# ST_LINK_V2-1.net
KiCad netlist of a schematic drawn in Altium Designer
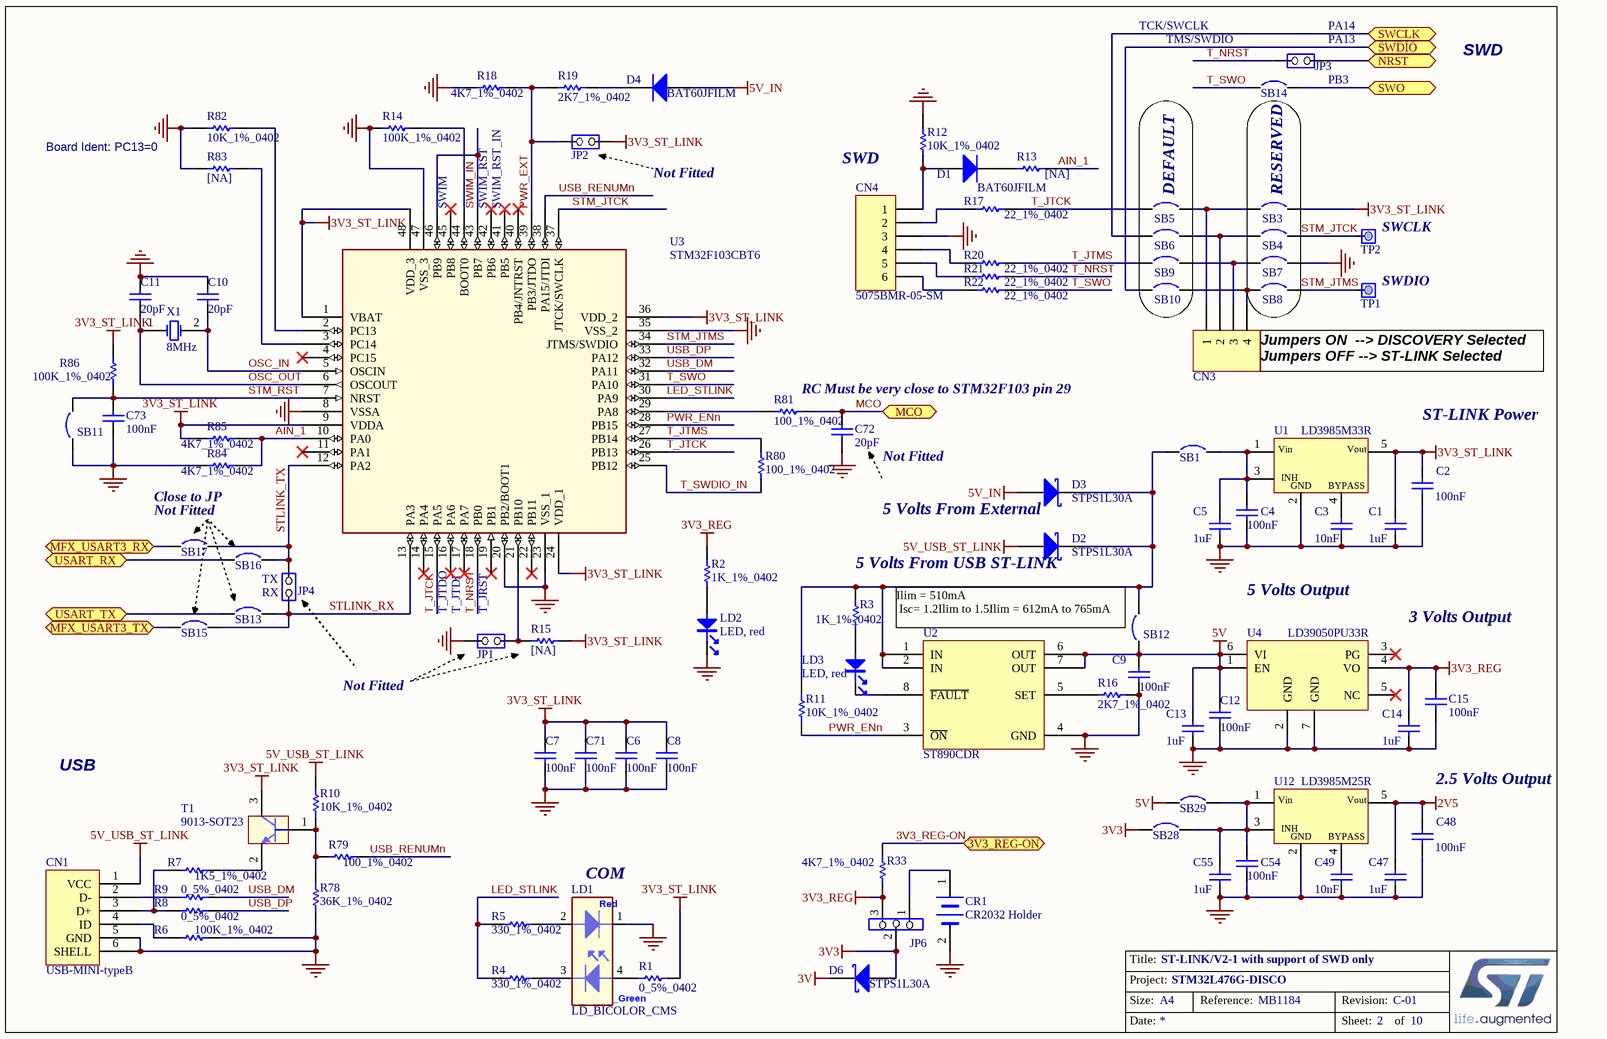
[diagram p0: ST_LINK_V2-1.SCHDOC]

(export (version "E")
  (design (tool "Eeschema 10.0.6"))
  (components
    (comp (ref "C1")
      (value "1uF")
      (footprint "0603C")
      (description "Capacitor,1uF,16V,X5R,10%,0603,YAGEO")
      (libsource (lib "MCD_TOOLS") (part "Cap_1uF_X5R_10%_0603"))
    )
    (comp (ref "C2")
      (value "100nF")
      (footprint "0402C")
      (description "Capacitor,100nF,16V,X7R,10%,0402,YAGEO")
      (libsource (lib "MCD_TOOLS") (part "Cap_100nF_X7R_10%_0402"))
    )
    (comp (ref "C3")
      (value "10nF")
      (footprint "0603C")
      (description "Capacitor,10nF,50V,X7R,10%,0603,YAGEO")
      (libsource (lib "MCD_TOOLS") (part "Cap_10nF_X7R_10%_0603"))
    )
    (comp (ref "C4")
      (value "100nF")
      (footprint "0402C")
      (description "Capacitor,100nF,16V,X7R,10%,0402,YAGEO")
      (libsource (lib "MCD_TOOLS") (part "Cap_100nF_X7R_10%_0402"))
    )
    (comp (ref "C5")
      (value "1uF")
      (footprint "0603C")
      (description "Capacitor,1uF,16V,X5R,10%,0603,YAGEO")
      (libsource (lib "MCD_TOOLS") (part "Cap_1uF_X5R_10%_0603"))
    )
    (comp (ref "C6")
      (value "100nF")
      (footprint "0402C")
      (description "Capacitor,100nF,16V,X7R,10%,0402,YAGEO")
      (libsource (lib "MCD_TOOLS") (part "Cap_100nF_X7R_10%_0402"))
    )
    (comp (ref "C7")
      (value "100nF")
      (footprint "0402C")
      (description "Capacitor,100nF,16V,X7R,10%,0402,YAGEO")
      (libsource (lib "MCD_TOOLS") (part "Cap_100nF_X7R_10%_0402"))
    )
    (comp (ref "C8")
      (value "100nF")
      (footprint "0402C")
      (description "Capacitor,100nF,16V,X7R,10%,0402,YAGEO")
      (libsource (lib "MCD_TOOLS") (part "Cap_100nF_X7R_10%_0402"))
    )
    (comp (ref "C9")
      (value "100nF")
      (footprint "0402C")
      (description "Capacitor,100nF,16V,X7R,10%,0402,YAGEO")
      (libsource (lib "MCD_TOOLS") (part "Cap_100nF_X7R_10%_0402"))
    )
    (comp (ref "C10")
      (value "20pF")
      (footprint "0402C")
      (description "Capacitor,20pF,50V,NPO,5%,0402,YAGEO")
      (libsource (lib "MCD_TOOLS") (part "Cap_20pF_NPO_5%_0402"))
    )
    (comp (ref "C11")
      (value "20pF")
      (footprint "0402C")
      (description "Capacitor,20pF,50V,NPO,5%,0402,YAGEO")
      (libsource (lib "MCD_TOOLS") (part "Cap_20pF_NPO_5%_0402"))
    )
    (comp (ref "C12")
      (value "100nF")
      (footprint "0402C")
      (description "Capacitor,100nF,16V,X7R,10%,0402,YAGEO")
      (libsource (lib "MCD_TOOLS") (part "Cap_100nF_X7R_10%_0402"))
    )
    (comp (ref "C13")
      (value "1uF")
      (footprint "0603C")
      (description "Capacitor,1uF,16V,X5R,10%,0603,YAGEO")
      (libsource (lib "MCD_TOOLS") (part "Cap_1uF_X5R_10%_0603"))
    )
    (comp (ref "C14")
      (value "1uF")
      (footprint "0603C")
      (description "Capacitor,1uF,16V,X5R,10%,0603,YAGEO")
      (libsource (lib "MCD_TOOLS") (part "Cap_1uF_X5R_10%_0603"))
    )
    (comp (ref "C15")
      (value "100nF")
      (footprint "0402C")
      (description "Capacitor,100nF,16V,X7R,10%,0402,YAGEO")
      (libsource (lib "MCD_TOOLS") (part "Cap_100nF_X7R_10%_0402"))
    )
    (comp (ref "C47")
      (value "1uF")
      (footprint "0603C")
      (description "Capacitor,1uF,16V,X5R,10%,0603,YAGEO")
      (libsource (lib "MCD_TOOLS") (part "Cap_1uF_X5R_10%_0603"))
    )
    (comp (ref "C48")
      (value "100nF")
      (footprint "0402C")
      (description "Capacitor,100nF,16V,X7R,10%,0402,YAGEO")
      (libsource (lib "MCD_TOOLS") (part "Cap_100nF_X7R_10%_0402"))
    )
    (comp (ref "C49")
      (value "10nF")
      (footprint "0603C")
      (description "Capacitor,10nF,50V,X7R,10%,0603,YAGEO")
      (libsource (lib "MCD_TOOLS") (part "Cap_10nF_X7R_10%_0603"))
    )
    (comp (ref "C54")
      (value "100nF")
      (footprint "0402C")
      (description "Capacitor,100nF,16V,X7R,10%,0402,YAGEO")
      (libsource (lib "MCD_TOOLS") (part "Cap_100nF_X7R_10%_0402"))
    )
    (comp (ref "C55")
      (value "1uF")
      (footprint "0603C")
      (description "Capacitor,1uF,16V,X5R,10%,0603,YAGEO")
      (libsource (lib "MCD_TOOLS") (part "Cap_1uF_X5R_10%_0603"))
    )
    (comp (ref "C71")
      (value "100nF")
      (footprint "0402C")
      (description "Capacitor,100nF,16V,X7R,10%,0402,YAGEO")
      (libsource (lib "MCD_TOOLS") (part "Cap_100nF_X7R_10%_0402"))
    )
    (comp (ref "C72")
      (value "20pF")
      (footprint "0402C")
      (description "Capacitor,20pF,50V,NPO,5%,0402,YAGEO")
      (libsource (lib "MCD_TOOLS") (part "Cap_20pF_NPO_5%_0402"))
    )
    (comp (ref "C73")
      (value "100nF")
      (footprint "0402C")
      (description "Capacitor,100nF,16V,X7R,10%,0402,YAGEO")
      (libsource (lib "MCD_TOOLS") (part "Cap_100nF_X7R_10%_0402"))
    )
    (comp (ref "CN1")
      (value "USB-MINI-typeB")
      (footprint "USB-MINI-B-SMD")
      (description "USB-MINI-typeB connector")
      (libsource (lib "MCD_TOOLS") (part "USB-MINI-typeB connector"))
    )
    (comp (ref "CN3")
      (value "Header 4")
      (footprint "Header 4")
      (description "Header, 4-Pin")
      (fields (field (name "PUBLISHER") "Altium Limited"))
      (libsource (lib "MCD_TOOLS") (part "Header 4"))
    )
    (comp (ref "CN4")
      (value "5075BMR-05-SM")
      (footprint "HDR1X6")
      (description "Header, 6-Pin")
      (fields (field (name "PUBLISHER") "Altium Limited"))
      (libsource (lib "MCD_TOOLS") (part "Header 6"))
    )
    (comp (ref "CR1")
      (value "CR2032 Holder")
      (footprint "CR2032/SMT")
      (description "CR2032 socket, S8421-45R")
      (libsource (lib "MCD_TOOLS") (part "BATT_2032"))
    )
    (comp (ref "D1")
      (value "BAT60JFILM")
      (footprint "SOD323/A")
      (libsource (lib "MCD_TOOLS") (part "BAT60JFILM"))
    )
    (comp (ref "D2")
      (value "STPS1L30A")
      (footprint "SMA")
      (description "Low Drop power Schottky rectifier")
      (libsource (lib "MCD_TOOLS") (part "STPS1L30A"))
    )
    (comp (ref "D3")
      (value "STPS1L30A")
      (footprint "SMA")
      (description "Low Drop power Schottky rectifier")
      (libsource (lib "MCD_TOOLS") (part "STPS1L30A"))
    )
    (comp (ref "D4")
      (value "BAT60JFILM")
      (footprint "SOD323/A")
      (libsource (lib "MCD_TOOLS") (part "BAT60JFILM"))
    )
    (comp (ref "D6")
      (value "STPS1L30A")
      (footprint "SMA")
      (description "Low Drop power Schottky rectifier")
      (libsource (lib "MCD_TOOLS") (part "STPS1L30A"))
    )
    (comp (ref "JP1")
      (value "Jumper 2 pins")
      (footprint "SIP2/2.54")
      (libsource (lib "MCD_TOOLS") (part "Jumper2"))
    )
    (comp (ref "JP2")
      (value "Jumper 2 pins")
      (footprint "SIP2/2.54")
      (libsource (lib "MCD_TOOLS") (part "Jumper2"))
    )
    (comp (ref "JP3")
      (value "Jumper 2 pins")
      (footprint "SIP2/2.54")
      (libsource (lib "MCD_TOOLS") (part "Jumper2"))
    )
    (comp (ref "JP4")
      (value "Jumper 2 pins")
      (footprint "SIP2/2.54")
      (libsource (lib "MCD_TOOLS") (part "Jumper2"))
    )
    (comp (ref "JP6")
      (value "Jumper 3 pins")
      (footprint "SIP3")
      (libsource (lib "MCD_TOOLS") (part "Jumper3"))
    )
    (comp (ref "LD1")
      (value "LD_BICOLOR_CMS")
      (footprint "HSMF-A201")
      (description "Bicolor Led")
      (libsource (lib "MCD_TOOLS") (part "LD_BICOLOR_CMS"))
    )
    (comp (ref "LD2")
      (value "LED, red")
      (footprint "0603D")
      (description "LED, red, 0603")
      (libsource (lib "MCD_TOOLS") (part "LED_red"))
    )
    (comp (ref "LD3")
      (value "LED, red")
      (footprint "0603D")
      (description "LED, red, 0603")
      (libsource (lib "MCD_TOOLS") (part "LED_red"))
    )
    (comp (ref "R1")
      (value "0_5%_0402")
      (footprint "0402R")
      (description "Resistor,0,0402,5%,YAGEO")
      (libsource (lib "MCD_TOOLS") (part "Res_0_5%_0402"))
    )
    (comp (ref "R2")
      (value "1K_1%_0402")
      (footprint "0402R")
      (description "Resistor,1K,0402,1%,YAGEO")
      (libsource (lib "MCD_TOOLS") (part "Res_1K_1%_0402"))
    )
    (comp (ref "R3")
      (value "1K_1%_0402")
      (footprint "0402R")
      (description "Resistor,1K,0402,1%,YAGEO")
      (libsource (lib "MCD_TOOLS") (part "Res_1K_1%_0402"))
    )
    (comp (ref "R4")
      (value "330_1%_0402")
      (footprint "0402R")
      (description "Resistor,330,0402,1%,YAGEO")
      (libsource (lib "MCD_TOOLS") (part "Res_330_1%_0402"))
    )
    (comp (ref "R5")
      (value "330_1%_0402")
      (footprint "0402R")
      (description "Resistor,330,0402,1%,YAGEO")
      (libsource (lib "MCD_TOOLS") (part "Res_330_1%_0402"))
    )
    (comp (ref "R6")
      (value "100K_1%_0402")
      (footprint "0402R")
      (description "Resistor,100K,0402,1%,YAGEO")
      (libsource (lib "MCD_TOOLS") (part "Res_100K_1%_0402"))
    )
    (comp (ref "R7")
      (value "1K5_1%_0402")
      (footprint "0402R")
      (description "Resistor,1K5,0402,1%,YAGEO")
      (libsource (lib "MCD_TOOLS") (part "Res_1K5_1%_0402"))
    )
    (comp (ref "R8")
      (value "0_5%_0402")
      (footprint "0402R")
      (description "Resistor,0,0402,5%,YAGEO")
      (libsource (lib "MCD_TOOLS") (part "Res_0_5%_0402"))
    )
    (comp (ref "R9")
      (value "0_5%_0402")
      (footprint "0402R")
      (description "Resistor,0,0402,5%,YAGEO")
      (libsource (lib "MCD_TOOLS") (part "Res_0_5%_0402"))
    )
    (comp (ref "R10")
      (value "10K_1%_0402")
      (footprint "0402R")
      (description "Resistor,10K,0402,1%,YAGEO")
      (libsource (lib "MCD_TOOLS") (part "Res_10K_1%_0402"))
    )
    (comp (ref "R11")
      (value "10K_1%_0402")
      (footprint "0402R")
      (description "Resistor,10K,0402,1%,YAGEO")
      (libsource (lib "MCD_TOOLS") (part "Res_10K_1%_0402"))
    )
    (comp (ref "R12")
      (value "10K_1%_0402")
      (footprint "0402R")
      (description "Resistor,10K,0402,1%,YAGEO")
      (libsource (lib "MCD_TOOLS") (part "Res_10K_1%_0402"))
    )
    (comp (ref "R13")
      (value "[NA]")
      (footprint "0402R")
      (description "Resistor,[NA],0402")
      (libsource (lib "MCD_TOOLS") (part "Res_NA_0402"))
    )
    (comp (ref "R14")
      (value "100K_1%_0402")
      (footprint "0402R")
      (description "Resistor,100K,0402,1%,YAGEO")
      (libsource (lib "MCD_TOOLS") (part "Res_100K_1%_0402"))
    )
    (comp (ref "R15")
      (value "[NA]")
      (footprint "0402R")
      (description "Resistor,[NA],0402")
      (libsource (lib "MCD_TOOLS") (part "Res_NA_0402"))
    )
    (comp (ref "R16")
      (value "2K7_1%_0402")
      (footprint "0402R")
      (description "Resistor,2K7,0402,1%,YAGEO")
      (libsource (lib "MCD_TOOLS") (part "Res_2K7_1%_0402"))
    )
    (comp (ref "R17")
      (value "22_1%_0402")
      (footprint "0402R")
      (description "Resistor,22,0402,1%,YAGEO")
      (libsource (lib "MCD_TOOLS") (part "Res_22_1%_0402"))
    )
    (comp (ref "R18")
      (value "4K7_1%_0402")
      (footprint "0402R")
      (description "Resistor,4K7,0402,1%,YAGEO")
      (libsource (lib "MCD_TOOLS") (part "Res_4K7_1%_0402"))
    )
    (comp (ref "R19")
      (value "2K7_1%_0402")
      (footprint "0402R")
      (description "Resistor,2K7,0402,1%,YAGEO")
      (libsource (lib "MCD_TOOLS") (part "Res_2K7_1%_0402"))
    )
    (comp (ref "R20")
      (value "22_1%_0402")
      (footprint "0402R")
      (description "Resistor,22,0402,1%,YAGEO")
      (libsource (lib "MCD_TOOLS") (part "Res_22_1%_0402"))
    )
    (comp (ref "R21")
      (value "22_1%_0402")
      (footprint "0402R")
      (description "Resistor,22,0402,1%,YAGEO")
      (libsource (lib "MCD_TOOLS") (part "Res_22_1%_0402"))
    )
    (comp (ref "R22")
      (value "22_1%_0402")
      (footprint "0402R")
      (description "Resistor,22,0402,1%,YAGEO")
      (libsource (lib "MCD_TOOLS") (part "Res_22_1%_0402"))
    )
    (comp (ref "R33")
      (value "4K7_1%_0402")
      (footprint "0402R")
      (description "Resistor,4K7,0402,1%,YAGEO")
      (libsource (lib "MCD_TOOLS") (part "Res_4K7_1%_0402"))
    )
    (comp (ref "R78")
      (value "36K_1%_0402")
      (footprint "0402R")
      (description "Resistor,36K,0402,1%,YAGEO")
      (libsource (lib "MCD_TOOLS") (part "Res_36K_1%_0402"))
    )
    (comp (ref "R79")
      (value "100_1%_0402")
      (footprint "0402R")
      (description "Resistor,100,0402,1%,YAGEO")
      (libsource (lib "MCD_TOOLS") (part "Res_100_1%_0402"))
    )
    (comp (ref "R80")
      (value "100_1%_0402")
      (footprint "0402R")
      (description "Resistor,100,0402,1%,YAGEO")
      (libsource (lib "MCD_TOOLS") (part "Res_100_1%_0402"))
    )
    (comp (ref "R81")
      (value "100_1%_0402")
      (footprint "0402R")
      (description "Resistor,100,0402,1%,YAGEO")
      (libsource (lib "MCD_TOOLS") (part "Res_100_1%_0402"))
    )
    (comp (ref "R82")
      (value "10K_1%_0402")
      (footprint "0402R")
      (description "Resistor,10K,0402,1%,YAGEO")
      (libsource (lib "MCD_TOOLS") (part "Res_10K_1%_0402"))
    )
    (comp (ref "R83")
      (value "[NA]")
      (footprint "0402R")
      (description "Resistor,[NA],0402")
      (libsource (lib "MCD_TOOLS") (part "Res_NA_0402"))
    )
    (comp (ref "R84")
      (value "4K7_1%_0402")
      (footprint "0402R")
      (description "Resistor,4K7,0402,1%,YAGEO")
      (libsource (lib "MCD_TOOLS") (part "Res_4K7_1%_0402"))
    )
    (comp (ref "R85")
      (value "4K7_1%_0402")
      (footprint "0402R")
      (description "Resistor,4K7,0402,1%,YAGEO")
      (libsource (lib "MCD_TOOLS") (part "Res_4K7_1%_0402"))
    )
    (comp (ref "R86")
      (value "100K_1%_0402")
      (footprint "0402R")
      (description "Resistor,100K,0402,1%,YAGEO")
      (libsource (lib "MCD_TOOLS") (part "Res_100K_1%_0402"))
    )
    (comp (ref "SB1")
      (value "Circuit Breaker")
      (footprint "JP2_SMD")
      (libsource (lib "MCD_TOOLS") (part "Circuit Breaker"))
    )
    (comp (ref "SB3")
      (value "Circuit Breaker")
      (footprint "JP2_SMD")
      (libsource (lib "MCD_TOOLS") (part "Circuit Breaker"))
    )
    (comp (ref "SB4")
      (value "Circuit Breaker")
      (footprint "JP2_SMD")
      (libsource (lib "MCD_TOOLS") (part "Circuit Breaker"))
    )
    (comp (ref "SB5")
      (value "Circuit Breaker")
      (footprint "JP2_SMD")
      (libsource (lib "MCD_TOOLS") (part "Circuit Breaker"))
    )
    (comp (ref "SB6")
      (value "Circuit Breaker")
      (footprint "JP2_SMD")
      (libsource (lib "MCD_TOOLS") (part "Circuit Breaker"))
    )
    (comp (ref "SB7")
      (value "Circuit Breaker")
      (footprint "JP2_SMD")
      (libsource (lib "MCD_TOOLS") (part "Circuit Breaker"))
    )
    (comp (ref "SB8")
      (value "Circuit Breaker")
      (footprint "JP2_SMD")
      (libsource (lib "MCD_TOOLS") (part "Circuit Breaker"))
    )
    (comp (ref "SB9")
      (value "Circuit Breaker")
      (footprint "JP2_SMD")
      (libsource (lib "MCD_TOOLS") (part "Circuit Breaker"))
    )
    (comp (ref "SB10")
      (value "Circuit Breaker")
      (footprint "JP2_SMD")
      (libsource (lib "MCD_TOOLS") (part "Circuit Breaker"))
    )
    (comp (ref "SB11")
      (value "Circuit Breaker")
      (footprint "JP2_SMD")
      (libsource (lib "MCD_TOOLS") (part "Circuit Breaker"))
    )
    (comp (ref "SB12")
      (value "Circuit Breaker")
      (footprint "JP2_SMD")
      (libsource (lib "MCD_TOOLS") (part "Circuit Breaker"))
    )
    (comp (ref "SB13")
      (value "Circuit Breaker")
      (footprint "JP2_SMD")
      (libsource (lib "MCD_TOOLS") (part "Circuit Breaker"))
    )
    (comp (ref "SB14")
      (value "Circuit Breaker")
      (footprint "JP2_SMD")
      (libsource (lib "MCD_TOOLS") (part "Circuit Breaker"))
    )
    (comp (ref "SB15")
      (value "Circuit Breaker")
      (footprint "JP2_SMD")
      (libsource (lib "MCD_TOOLS") (part "Circuit Breaker"))
    )
    (comp (ref "SB16")
      (value "Circuit Breaker")
      (footprint "JP2_SMD")
      (libsource (lib "MCD_TOOLS") (part "Circuit Breaker"))
    )
    (comp (ref "SB17")
      (value "Circuit Breaker")
      (footprint "JP2_SMD")
      (libsource (lib "MCD_TOOLS") (part "Circuit Breaker"))
    )
    (comp (ref "SB28")
      (value "Circuit Breaker")
      (footprint "JP2_SMD")
      (libsource (lib "MCD_TOOLS") (part "Circuit Breaker"))
    )
    (comp (ref "SB29")
      (value "Circuit Breaker")
      (footprint "JP2_SMD")
      (libsource (lib "MCD_TOOLS") (part "Circuit Breaker"))
    )
    (comp (ref "T1")
      (value "9013-SOT23")
      (footprint "SOT23")
      (description "NPN Bipolar Transistor")
      (libsource (lib "MCD_TOOLS") (part "9013-SOT23"))
    )
    (comp (ref "TP1")
      (value "Test point 1 pin with hole")
      (footprint "SIP1/2.54")
      (description "Test Point")
      (libsource (lib "MCD_TOOLS") (part "TP1"))
    )
    (comp (ref "TP2")
      (value "Test point 1 pin with hole")
      (footprint "SIP1/2.54")
      (description "Test Point")
      (libsource (lib "MCD_TOOLS") (part "TP1"))
    )
    (comp (ref "U1")
      (value "LD3985M33R")
      (footprint "SOT-23-5L")
      (description "Ultra low drop-low noise BiCMOS voltage, regulators low ESR capacitors compatible")
      (libsource (lib "MCD_TOOLS") (part "LD3985M33R"))
    )
    (comp (ref "U2")
      (value "ST890CDR")
      (footprint "SO-8")
      (description "1.2 A current limited high-side power switch with thermal shutdown")
      (libsource (lib "MCD_TOOLS") (part "ST890CDR"))
    )
    (comp (ref "U3")
      (value "STM32F103CBT6")
      (footprint "QFP48 7x7")
      (description "Medium-density performance line ARM-based 32-bit MCU with 128KB Flash")
      (libsource (lib "MCD_TOOLS") (part "STM32F103CBT6"))
    )
    (comp (ref "U4")
      (value "LD39050PU33R")
      (footprint "DFN6_3x3")
      (description "Ultra low drop-low , 500 mA low quiescent current")
      (libsource (lib "MCD_TOOLS") (part "LD39050P"))
    )
    (comp (ref "U12")
      (value "LD3985M25R")
      (footprint "SOT-23-5L")
      (description "Ultra low drop-low noise BiCMOS voltage, regulators low ESR capacitors compatible")
      (libsource (lib "MCD_TOOLS") (part "LD3985M25R"))
    )
    (comp (ref "X1")
      (value "8MHz")
      (footprint "XTAL1")
      (description "Crystal Oscillator,8Mhz,20PF,20PPM,-10-70 degree,DIP,HC-49S")
      (libsource (lib "MCD_TOOLS") (part "XTAL_8MHZ_20PPM"))
    )
  )
  (nets
    (net (code "1") (name "/3V3_REG-ON") (class "Default")
      (node (ref "R33") (pin "2") (pinfunction "2_2") (pintype "passive"))
    )
    (net (code "2") (name "/AIN_1") (class "Default")
      (node (ref "R13") (pin "2") (pinfunction "2_2") (pintype "passive"))
      (node (ref "R84") (pin "2") (pinfunction "2_2") (pintype "passive"))
      (node (ref "R85") (pin "2") (pinfunction "2_2") (pintype "passive"))
      (node (ref "U3") (pin "10") (pinfunction "PA0_10") (pintype "bidirectional"))
    )
    (net (code "3") (name "/LED_STLINK") (class "Default")
      (node (ref "R4") (pin "1") (pinfunction "1_1") (pintype "passive"))
      (node (ref "R5") (pin "1") (pinfunction "1_1") (pintype "passive"))
      (node (ref "U3") (pin "30") (pinfunction "PA9_30") (pintype "bidirectional"))
    )
    (net (code "4") (name "/MCO") (class "Default")
      (node (ref "C72") (pin "1") (pinfunction "1_1") (pintype "passive"))
      (node (ref "R81") (pin "2") (pinfunction "2_2") (pintype "passive"))
    )
    (net (code "5") (name "/MFX_USART3_RX") (class "Default")
      (node (ref "SB17") (pin "1") (pinfunction "1_1") (pintype "passive"))
    )
    (net (code "6") (name "/MFX_USART3_TX") (class "Default")
      (node (ref "SB15") (pin "1") (pinfunction "1_1") (pintype "passive"))
    )
    (net (code "7") (name "/NRST") (class "Default")
      (node (ref "JP3") (pin "2") (pinfunction "NO_2") (pintype "passive"))
    )
    (net (code "8") (name "/OSC_IN") (class "Default")
      (node (ref "C10") (pin "2") (pinfunction "2_2") (pintype "passive"))
      (node (ref "U3") (pin "5") (pinfunction "OSCIN_5") (pintype "input"))
      (node (ref "X1") (pin "2") (pinfunction "OSC2_2") (pintype "passive"))
    )
    (net (code "9") (name "/OSC_OUT") (class "Default")
      (node (ref "C11") (pin "2") (pinfunction "2_2") (pintype "passive"))
      (node (ref "U3") (pin "6") (pinfunction "OSCOUT_6") (pintype "output"))
      (node (ref "X1") (pin "1") (pinfunction "OSC1_1") (pintype "passive"))
    )
    (net (code "10") (name "/PWR_ENn") (class "Default")
      (node (ref "R11") (pin "1") (pinfunction "1_1") (pintype "passive"))
      (node (ref "U2") (pin "3") (pinfunction "~{ON}_3") (pintype "passive"))
      (node (ref "U3") (pin "28") (pinfunction "PB15_28") (pintype "bidirectional"))
    )
    (net (code "11") (name "/PWR_EXT") (class "Default")
      (node (ref "JP2") (pin "1") (pinfunction "COMMON_1") (pintype "passive"))
      (node (ref "R18") (pin "2") (pinfunction "2_2") (pintype "passive"))
      (node (ref "R19") (pin "1") (pinfunction "1_1") (pintype "passive"))
      (node (ref "U3") (pin "39") (pinfunction "PB3/JTDO_39") (pintype "bidirectional"))
    )
    (net (code "12") (name "/STLINK_RX") (class "Default")
      (node (ref "JP4") (pin "1") (pinfunction "COMMON_1") (pintype "passive"))
      (node (ref "SB13") (pin "2") (pinfunction "2_2") (pintype "passive"))
      (node (ref "SB15") (pin "2") (pinfunction "2_2") (pintype "passive"))
      (node (ref "U3") (pin "13") (pinfunction "PA3_13") (pintype "bidirectional"))
    )
    (net (code "13") (name "/STLINK_TX") (class "Default")
      (node (ref "JP4") (pin "2") (pinfunction "NO_2") (pintype "passive"))
      (node (ref "SB16") (pin "2") (pinfunction "2_2") (pintype "passive"))
      (node (ref "SB17") (pin "2") (pinfunction "2_2") (pintype "passive"))
      (node (ref "U3") (pin "12") (pinfunction "PA2_12") (pintype "bidirectional"))
    )
    (net (code "14") (name "/STM_JTCK") (class "Default")
      (node (ref "SB4") (pin "2") (pinfunction "2_2") (pintype "passive"))
      (node (ref "TP2") (pin "1") (pinfunction "COMMON_1") (pintype "passive"))
      (node (ref "U3") (pin "37") (pinfunction "JTCK/SWCLK_37") (pintype "bidirectional"))
    )
    (net (code "15") (name "/STM_JTMS") (class "Default")
      (node (ref "SB8") (pin "2") (pinfunction "2_2") (pintype "passive"))
      (node (ref "TP1") (pin "1") (pinfunction "COMMON_1") (pintype "passive"))
      (node (ref "U3") (pin "34") (pinfunction "JTMS/SWDIO_34") (pintype "bidirectional"))
    )
    (net (code "16") (name "/STM_RST") (class "Default")
      (node (ref "C73") (pin "2") (pinfunction "2_2") (pintype "passive"))
      (node (ref "R86") (pin "1") (pinfunction "1_1") (pintype "passive"))
      (node (ref "SB11") (pin "2") (pinfunction "2_2") (pintype "passive"))
      (node (ref "U3") (pin "7") (pinfunction "NRST_7") (pintype "input"))
    )
    (net (code "17") (name "/SWCLK") (class "Default")
      (node (ref "SB6") (pin "1") (pinfunction "1_1") (pintype "passive"))
    )
    (net (code "18") (name "/SWDIO") (class "Default")
      (node (ref "SB10") (pin "1") (pinfunction "1_1") (pintype "passive"))
    )
    (net (code "19") (name "/SWIM_IN") (class "Default")
      (node (ref "U3") (pin "43") (pinfunction "PB7_43") (pintype "bidirectional"))
      (node (ref "U3") (pin "46") (pinfunction "PB9_46") (pintype "bidirectional"))
    )
    (net (code "20") (name "/SWO") (class "Default")
      (node (ref "SB14") (pin "2") (pinfunction "2_2") (pintype "passive"))
    )
    (net (code "21") (name "/T_JTCK") (class "Default")
      (node (ref "R17") (pin "2") (pinfunction "2_2") (pintype "passive"))
      (node (ref "SB5") (pin "1") (pinfunction "1_1") (pintype "passive"))
      (node (ref "U3") (pin "15") (pinfunction "PA5_15") (pintype "bidirectional"))
      (node (ref "U3") (pin "26") (pinfunction "PB13_26") (pintype "bidirectional"))
    )
    (net (code "22") (name "/T_JTMS") (class "Default")
      (node (ref "R20") (pin "2") (pinfunction "2_2") (pintype "passive"))
      (node (ref "R80") (pin "2") (pinfunction "2_2") (pintype "passive"))
      (node (ref "SB9") (pin "1") (pinfunction "1_1") (pintype "passive"))
      (node (ref "U3") (pin "27") (pinfunction "PB14_27") (pintype "bidirectional"))
    )
    (net (code "23") (name "/T_NRST") (class "Default")
      (node (ref "JP3") (pin "1") (pinfunction "COMMON_1") (pintype "passive"))
      (node (ref "R21") (pin "2") (pinfunction "2_2") (pintype "passive"))
      (node (ref "U3") (pin "18") (pinfunction "PB0_18") (pintype "bidirectional"))
    )
    (net (code "24") (name "/T_SWDIO_IN") (class "Default")
      (node (ref "R80") (pin "1") (pinfunction "1_1") (pintype "passive"))
      (node (ref "U3") (pin "25") (pinfunction "PB12_25") (pintype "bidirectional"))
    )
    (net (code "25") (name "/T_SWO") (class "Default")
      (node (ref "R22") (pin "2") (pinfunction "2_2") (pintype "passive"))
      (node (ref "SB14") (pin "1") (pinfunction "1_1") (pintype "passive"))
      (node (ref "U3") (pin "31") (pinfunction "PA10_31") (pintype "bidirectional"))
    )
    (net (code "26") (name "/USART_RX") (class "Default")
      (node (ref "SB16") (pin "1") (pinfunction "1_1") (pintype "passive"))
    )
    (net (code "27") (name "/USART_TX") (class "Default")
      (node (ref "SB13") (pin "1") (pinfunction "1_1") (pintype "passive"))
    )
    (net (code "28") (name "/USB_DM") (class "Default")
      (node (ref "R9") (pin "2") (pinfunction "2_2") (pintype "passive"))
      (node (ref "U3") (pin "32") (pinfunction "PA11_32") (pintype "bidirectional"))
    )
    (net (code "29") (name "/USB_DP") (class "Default")
      (node (ref "R8") (pin "2") (pinfunction "2_2") (pintype "passive"))
      (node (ref "U3") (pin "33") (pinfunction "PA12_33") (pintype "bidirectional"))
    )
    (net (code "30") (name "/USB_RENUMn") (class "Default")
      (node (ref "R79") (pin "2") (pinfunction "2_2") (pintype "passive"))
      (node (ref "U3") (pin "38") (pinfunction "PA15/JTDI_38") (pintype "bidirectional"))
    )
    (net (code "31") (name "2V5") (class "Default")
      (node (ref "C47") (pin "1") (pinfunction "1_1") (pintype "passive"))
      (node (ref "C48") (pin "2") (pinfunction "2_2") (pintype "passive"))
      (node (ref "U12") (pin "5") (pinfunction "Vout_5") (pintype "passive"))
    )
    (net (code "32") (name "3V") (class "Default")
      (node (ref "D6") (pin "2") (pinfunction "K_2") (pintype "passive"))
    )
    (net (code "33") (name "3V3") (class "Default")
      (node (ref "D6") (pin "1") (pinfunction "A_1") (pintype "passive"))
      (node (ref "JP6") (pin "2") (pintype "passive"))
      (node (ref "SB28") (pin "1") (pinfunction "1_1") (pintype "passive"))
    )
    (net (code "34") (name "3V3_REG") (class "Default")
      (node (ref "C14") (pin "2") (pinfunction "2_2") (pintype "passive"))
      (node (ref "C15") (pin "2") (pinfunction "2_2") (pintype "passive"))
      (node (ref "JP6") (pin "3") (pintype "passive"))
      (node (ref "R2") (pin "2") (pinfunction "2_2") (pintype "passive"))
      (node (ref "R33") (pin "1") (pinfunction "1_1") (pintype "passive"))
      (node (ref "U4") (pin "4") (pinfunction "VO_4") (pintype "passive"))
    )
    (net (code "35") (name "3V3_ST_LINK") (class "Default")
      (node (ref "C1") (pin "1") (pinfunction "1_1") (pintype "passive"))
      (node (ref "C2") (pin "2") (pinfunction "2_2") (pintype "passive"))
      (node (ref "C6") (pin "1") (pinfunction "1_1") (pintype "passive"))
      (node (ref "C7") (pin "2") (pinfunction "2_2") (pintype "passive"))
      (node (ref "C71") (pin "2") (pinfunction "2_2") (pintype "passive"))
      (node (ref "C8") (pin "2") (pinfunction "2_2") (pintype "passive"))
      (node (ref "JP2") (pin "2") (pinfunction "NO_2") (pintype "passive"))
      (node (ref "R1") (pin "2") (pinfunction "2_2") (pintype "passive"))
      (node (ref "R15") (pin "2") (pinfunction "2_2") (pintype "passive"))
      (node (ref "R85") (pin "1") (pinfunction "1_1") (pintype "passive"))
      (node (ref "R86") (pin "2") (pinfunction "2_2") (pintype "passive"))
      (node (ref "SB3") (pin "2") (pinfunction "2_2") (pintype "passive"))
      (node (ref "T1") (pin "3") (pinfunction "C_3") (pintype "passive"))
      (node (ref "U1") (pin "5") (pinfunction "Vout_5") (pintype "passive"))
      (node (ref "U3") (pin "1") (pinfunction "VBAT_1") (pintype "power_in"))
      (node (ref "U3") (pin "24") (pinfunction "VDD_1_24") (pintype "power_in"))
      (node (ref "U3") (pin "36") (pinfunction "VDD_2_36") (pintype "power_in"))
      (node (ref "U3") (pin "48") (pinfunction "VDD_3_48") (pintype "power_in"))
      (node (ref "U3") (pin "9") (pinfunction "VDDA_9") (pintype "power_in"))
    )
    (net (code "36") (name "5V") (class "Default")
      (node (ref "C12") (pin "2") (pinfunction "2_2") (pintype "passive"))
      (node (ref "C13") (pin "2") (pinfunction "2_2") (pintype "passive"))
      (node (ref "C9") (pin "2") (pinfunction "2_2") (pintype "passive"))
      (node (ref "SB12") (pin "1") (pinfunction "1_1") (pintype "passive"))
      (node (ref "SB29") (pin "1") (pinfunction "1_1") (pintype "passive"))
      (node (ref "U2") (pin "6") (pinfunction "OUT_6") (pintype "passive"))
      (node (ref "U2") (pin "7") (pinfunction "OUT_7") (pintype "passive"))
      (node (ref "U4") (pin "1") (pinfunction "EN_1") (pintype "passive"))
      (node (ref "U4") (pin "6") (pinfunction "VI_6") (pintype "passive"))
    )
    (net (code "37") (name "5V_IN") (class "Default")
      (node (ref "D3") (pin "1") (pinfunction "A_1") (pintype "passive"))
      (node (ref "D4") (pin "1") (pinfunction "A_1") (pintype "passive"))
    )
    (net (code "38") (name "5V_USB_ST_LINK") (class "Default")
      (node (ref "CN1") (pin "1") (pinfunction "VCC_1") (pintype "power_in"))
      (node (ref "D2") (pin "1") (pinfunction "A_1") (pintype "passive"))
      (node (ref "R10") (pin "2") (pinfunction "2_2") (pintype "passive"))
    )
    (net (code "39") (name "GND") (class "Default")
      (node (ref "C1") (pin "2") (pinfunction "2_2") (pintype "passive"))
      (node (ref "C10") (pin "1") (pinfunction "1_1") (pintype "passive"))
      (node (ref "C11") (pin "1") (pinfunction "1_1") (pintype "passive"))
      (node (ref "C12") (pin "1") (pinfunction "1_1") (pintype "passive"))
      (node (ref "C13") (pin "1") (pinfunction "1_1") (pintype "passive"))
      (node (ref "C14") (pin "1") (pinfunction "1_1") (pintype "passive"))
      (node (ref "C15") (pin "1") (pinfunction "1_1") (pintype "passive"))
      (node (ref "C2") (pin "1") (pinfunction "1_1") (pintype "passive"))
      (node (ref "C3") (pin "1") (pinfunction "1_1") (pintype "passive"))
      (node (ref "C4") (pin "1") (pinfunction "1_1") (pintype "passive"))
      (node (ref "C47") (pin "2") (pinfunction "2_2") (pintype "passive"))
      (node (ref "C48") (pin "1") (pinfunction "1_1") (pintype "passive"))
      (node (ref "C49") (pin "1") (pinfunction "1_1") (pintype "passive"))
      (node (ref "C5") (pin "1") (pinfunction "1_1") (pintype "passive"))
      (node (ref "C54") (pin "1") (pinfunction "1_1") (pintype "passive"))
      (node (ref "C55") (pin "1") (pinfunction "1_1") (pintype "passive"))
      (node (ref "C6") (pin "2") (pinfunction "2_2") (pintype "passive"))
      (node (ref "C7") (pin "1") (pinfunction "1_1") (pintype "passive"))
      (node (ref "C71") (pin "1") (pinfunction "1_1") (pintype "passive"))
      (node (ref "C72") (pin "2") (pinfunction "2_2") (pintype "passive"))
      (node (ref "C73") (pin "1") (pinfunction "1_1") (pintype "passive"))
      (node (ref "C8") (pin "1") (pinfunction "1_1") (pintype "passive"))
      (node (ref "C9") (pin "1") (pinfunction "1_1") (pintype "passive"))
      (node (ref "CN1") (pin "5") (pinfunction "GND_5") (pintype "passive"))
      (node (ref "CN1") (pin "6") (pinfunction "SHELL_6") (pintype "passive"))
      (node (ref "CN4") (pin "3") (pinfunction "3_3") (pintype "passive"))
      (node (ref "CR1") (pin "2") (pinfunction "-_2") (pintype "passive"))
      (node (ref "JP1") (pin "1") (pinfunction "COMMON_1") (pintype "passive"))
      (node (ref "LD1") (pin "1") (pinfunction "1_1") (pintype "passive"))
      (node (ref "LD2") (pin "2") (pintype "passive"))
      (node (ref "R12") (pin "2") (pinfunction "2_2") (pintype "passive"))
      (node (ref "R14") (pin "1") (pinfunction "1_1") (pintype "passive"))
      (node (ref "R16") (pin "2") (pinfunction "2_2") (pintype "passive"))
      (node (ref "R18") (pin "1") (pinfunction "1_1") (pintype "passive"))
      (node (ref "R6") (pin "2") (pinfunction "2_2") (pintype "passive"))
      (node (ref "R78") (pin "1") (pinfunction "1_1") (pintype "passive"))
      (node (ref "R82") (pin "1") (pinfunction "1_1") (pintype "passive"))
      (node (ref "R83") (pin "1") (pinfunction "1_1") (pintype "passive"))
      (node (ref "R84") (pin "1") (pinfunction "1_1") (pintype "passive"))
      (node (ref "SB11") (pin "1") (pinfunction "1_1") (pintype "passive"))
      (node (ref "SB7") (pin "2") (pinfunction "2_2") (pintype "passive"))
      (node (ref "U1") (pin "2") (pinfunction "GND_2") (pintype "passive"))
      (node (ref "U12") (pin "2") (pinfunction "GND_2") (pintype "passive"))
      (node (ref "U2") (pin "4") (pinfunction "GND_4") (pintype "passive"))
      (node (ref "U3") (pin "20") (pinfunction "PB2/BOOT1_20") (pintype "bidirectional"))
      (node (ref "U3") (pin "23") (pinfunction "VSS_1_23") (pintype "power_in"))
      (node (ref "U3") (pin "35") (pinfunction "VSS_2_35") (pintype "power_in"))
      (node (ref "U3") (pin "47") (pinfunction "VSS_3_47") (pintype "power_in"))
      (node (ref "U3") (pin "8") (pinfunction "VSSA_8") (pintype "power_in"))
      (node (ref "U4") (pin "2") (pinfunction "GND_2") (pintype "passive"))
      (node (ref "U4") (pin "7") (pinfunction "GND_7") (pintype "passive"))
    )
    (net (code "40") (name "Net-(CN1-D+)") (class "Default")
      (node (ref "CN1") (pin "3") (pinfunction "D+_3") (pintype "passive"))
      (node (ref "R7") (pin "1") (pinfunction "1_1") (pintype "passive"))
      (node (ref "R8") (pin "1") (pinfunction "1_1") (pintype "passive"))
    )
    (net (code "41") (name "Net-(CN1-D-)") (class "Default")
      (node (ref "CN1") (pin "2") (pinfunction "D-_2") (pintype "passive"))
      (node (ref "R9") (pin "1") (pinfunction "1_1") (pintype "passive"))
    )
    (net (code "42") (name "Net-(CN1-ID)") (class "Default")
      (node (ref "CN1") (pin "4") (pinfunction "ID_4") (pintype "passive"))
      (node (ref "R6") (pin "1") (pinfunction "1_1") (pintype "passive"))
    )
    (net (code "43") (name "Net-(CN3-Pad1)") (class "Default")
      (node (ref "CN3") (pin "1") (pinfunction "1_1") (pintype "passive"))
      (node (ref "SB3") (pin "1") (pinfunction "1_1") (pintype "passive"))
      (node (ref "SB5") (pin "2") (pinfunction "2_2") (pintype "passive"))
    )
    (net (code "44") (name "Net-(CN3-Pad2)") (class "Default")
      (node (ref "CN3") (pin "2") (pinfunction "2_2") (pintype "passive"))
      (node (ref "SB4") (pin "1") (pinfunction "1_1") (pintype "passive"))
      (node (ref "SB6") (pin "2") (pinfunction "2_2") (pintype "passive"))
    )
    (net (code "45") (name "Net-(CN3-Pad3)") (class "Default")
      (node (ref "CN3") (pin "3") (pinfunction "3_3") (pintype "passive"))
      (node (ref "SB7") (pin "1") (pinfunction "1_1") (pintype "passive"))
      (node (ref "SB9") (pin "2") (pinfunction "2_2") (pintype "passive"))
    )
    (net (code "46") (name "Net-(CN3-Pad4)") (class "Default")
      (node (ref "CN3") (pin "4") (pinfunction "4_4") (pintype "passive"))
      (node (ref "SB10") (pin "2") (pinfunction "2_2") (pintype "passive"))
      (node (ref "SB8") (pin "1") (pinfunction "1_1") (pintype "passive"))
    )
    (net (code "47") (name "Net-(CN4-Pad2)") (class "Default")
      (node (ref "CN4") (pin "2") (pinfunction "2_2") (pintype "passive"))
      (node (ref "R17") (pin "1") (pinfunction "1_1") (pintype "passive"))
    )
    (net (code "48") (name "Net-(CN4-Pad4)") (class "Default")
      (node (ref "CN4") (pin "4") (pinfunction "4_4") (pintype "passive"))
      (node (ref "R20") (pin "1") (pinfunction "1_1") (pintype "passive"))
    )
    (net (code "49") (name "Net-(CN4-Pad5)") (class "Default")
      (node (ref "CN4") (pin "5") (pinfunction "5_5") (pintype "passive"))
      (node (ref "R21") (pin "1") (pinfunction "1_1") (pintype "passive"))
    )
    (net (code "50") (name "Net-(CN4-Pad6)") (class "Default")
      (node (ref "CN4") (pin "6") (pinfunction "6_6") (pintype "passive"))
      (node (ref "R22") (pin "1") (pinfunction "1_1") (pintype "passive"))
    )
    (net (code "51") (name "Net-(CR1-+)") (class "Default")
      (node (ref "CR1") (pin "1") (pinfunction "+_1") (pintype "passive"))
      (node (ref "JP6") (pin "1") (pintype "passive"))
    )
    (net (code "52") (name "Net-(D1-A)") (class "Default")
      (node (ref "CN4") (pin "1") (pinfunction "1_1") (pintype "passive"))
      (node (ref "D1") (pin "1") (pinfunction "A_1") (pintype "passive"))
      (node (ref "R12") (pin "1") (pinfunction "1_1") (pintype "passive"))
    )
    (net (code "53") (name "Net-(D1-K)") (class "Default")
      (node (ref "D1") (pin "2") (pinfunction "K_2") (pintype "passive"))
      (node (ref "R13") (pin "1") (pinfunction "1_1") (pintype "passive"))
    )
    (net (code "54") (name "Net-(D2-K)") (class "Default")
      (node (ref "D2") (pin "2") (pinfunction "K_2") (pintype "passive"))
      (node (ref "D3") (pin "2") (pinfunction "K_2") (pintype "passive"))
      (node (ref "R11") (pin "2") (pinfunction "2_2") (pintype "passive"))
      (node (ref "R3") (pin "2") (pinfunction "2_2") (pintype "passive"))
      (node (ref "SB1") (pin "1") (pinfunction "1_1") (pintype "passive"))
      (node (ref "SB12") (pin "2") (pinfunction "2_2") (pintype "passive"))
      (node (ref "U2") (pin "1") (pinfunction "IN_1") (pintype "passive"))
      (node (ref "U2") (pin "2") (pinfunction "IN_2") (pintype "passive"))
    )
    (net (code "55") (name "Net-(D4-K)") (class "Default")
      (node (ref "D4") (pin "2") (pinfunction "K_2") (pintype "passive"))
      (node (ref "R19") (pin "2") (pinfunction "2_2") (pintype "passive"))
    )
    (net (code "56") (name "Net-(JP1-NO)") (class "Default")
      (node (ref "JP1") (pin "2") (pinfunction "NO_2") (pintype "passive"))
      (node (ref "R15") (pin "1") (pinfunction "1_1") (pintype "passive"))
      (node (ref "U3") (pin "21") (pinfunction "PB10_21") (pintype "bidirectional"))
    )
    (net (code "57") (name "Net-(LD1-Pad2)") (class "Default")
      (node (ref "LD1") (pin "2") (pinfunction "2_2") (pintype "passive"))
      (node (ref "R5") (pin "2") (pinfunction "2_2") (pintype "passive"))
    )
    (net (code "58") (name "Net-(LD1-Pad3)") (class "Default")
      (node (ref "LD1") (pin "3") (pinfunction "3_3") (pintype "passive"))
      (node (ref "R4") (pin "2") (pinfunction "2_2") (pintype "passive"))
    )
    (net (code "59") (name "Net-(LD1-Pad4)") (class "Default")
      (node (ref "LD1") (pin "4") (pinfunction "4_4") (pintype "passive"))
      (node (ref "R1") (pin "1") (pinfunction "1_1") (pintype "passive"))
    )
    (net (code "60") (name "Net-(LD2-Pad1)") (class "Default")
      (node (ref "LD2") (pin "1") (pintype "passive"))
      (node (ref "R2") (pin "1") (pinfunction "1_1") (pintype "passive"))
    )
    (net (code "61") (name "Net-(LD3-Pad1)") (class "Default")
      (node (ref "LD3") (pin "1") (pintype "passive"))
      (node (ref "R3") (pin "1") (pinfunction "1_1") (pintype "passive"))
    )
    (net (code "62") (name "Net-(T1-B)") (class "Default")
      (node (ref "R10") (pin "1") (pinfunction "1_1") (pintype "passive"))
      (node (ref "R78") (pin "2") (pinfunction "2_2") (pintype "passive"))
      (node (ref "R79") (pin "1") (pinfunction "1_1") (pintype "passive"))
      (node (ref "T1") (pin "1") (pinfunction "B_1") (pintype "passive"))
    )
    (net (code "63") (name "Net-(T1-E)") (class "Default")
      (node (ref "R7") (pin "2") (pinfunction "2_2") (pintype "passive"))
      (node (ref "T1") (pin "2") (pinfunction "E_2") (pintype "passive"))
    )
    (net (code "64") (name "Net-(U1-BYPASS)") (class "Default")
      (node (ref "C3") (pin "2") (pinfunction "2_2") (pintype "passive"))
      (node (ref "U1") (pin "4") (pinfunction "BYPASS_4") (pintype "passive"))
    )
    (net (code "65") (name "Net-(U1-CE)") (class "Default")
      (node (ref "C4") (pin "2") (pinfunction "2_2") (pintype "passive"))
      (node (ref "C5") (pin "2") (pinfunction "2_2") (pintype "passive"))
      (node (ref "SB1") (pin "2") (pinfunction "2_2") (pintype "passive"))
      (node (ref "U1") (pin "1") (pinfunction "Vin_1") (pintype "passive"))
      (node (ref "U1") (pin "3") (pinfunction "CE_3") (pintype "passive"))
    )
    (net (code "66") (name "Net-(U2-SET)") (class "Default")
      (node (ref "R16") (pin "1") (pinfunction "1_1") (pintype "passive"))
      (node (ref "U2") (pin "5") (pinfunction "SET_5") (pintype "passive"))
    )
    (net (code "67") (name "Net-(U2-~{FAULT})") (class "Default")
      (node (ref "LD3") (pin "2") (pintype "passive"))
      (node (ref "U2") (pin "8") (pinfunction "~{FAULT}_8") (pintype "passive"))
    )
    (net (code "68") (name "Net-(U3-BOOT0)") (class "Default")
      (node (ref "R14") (pin "2") (pinfunction "2_2") (pintype "passive"))
      (node (ref "U3") (pin "44") (pinfunction "BOOT0_44") (pintype "bidirectional"))
    )
    (net (code "69") (name "Net-(U3-PA8)") (class "Default")
      (node (ref "R81") (pin "1") (pinfunction "1_1") (pintype "passive"))
      (node (ref "U3") (pin "29") (pinfunction "PA8_29") (pintype "bidirectional"))
    )
    (net (code "70") (name "Net-(U3-PC13)") (class "Default")
      (node (ref "R82") (pin "2") (pinfunction "2_2") (pintype "passive"))
      (node (ref "U3") (pin "2") (pinfunction "PC13_2") (pintype "bidirectional"))
    )
    (net (code "71") (name "Net-(U3-PC14)") (class "Default")
      (node (ref "R83") (pin "2") (pinfunction "2_2") (pintype "passive"))
      (node (ref "U3") (pin "3") (pinfunction "PC14_3") (pintype "bidirectional"))
    )
    (net (code "72") (name "Net-(U12-BYPASS)") (class "Default")
      (node (ref "C49") (pin "2") (pinfunction "2_2") (pintype "passive"))
      (node (ref "U12") (pin "4") (pinfunction "BYPASS_4") (pintype "passive"))
    )
    (net (code "73") (name "Net-(U12-CE)") (class "Default")
      (node (ref "C54") (pin "2") (pinfunction "2_2") (pintype "passive"))
      (node (ref "C55") (pin "2") (pinfunction "2_2") (pintype "passive"))
      (node (ref "SB28") (pin "2") (pinfunction "2_2") (pintype "passive"))
      (node (ref "SB29") (pin "2") (pinfunction "2_2") (pintype "passive"))
      (node (ref "U12") (pin "1") (pinfunction "Vin_1") (pintype "passive"))
      (node (ref "U12") (pin "3") (pinfunction "CE_3") (pintype "passive"))
    )
    (net (code "74") (name "unconnected-(U3-PA1-Pad11)") (class "Default")
      (node (ref "U3") (pin "11") (pinfunction "PA1_11") (pintype "bidirectional+no_connect"))
    )
    (net (code "75") (name "unconnected-(U3-PA4-Pad14)") (class "Default")
      (node (ref "U3") (pin "14") (pinfunction "PA4_14") (pintype "bidirectional+no_connect"))
    )
    (net (code "76") (name "unconnected-(U3-PA6-Pad16)") (class "Default")
      (node (ref "U3") (pin "16") (pinfunction "PA6_16") (pintype "bidirectional+no_connect"))
    )
    (net (code "77") (name "unconnected-(U3-PA7-Pad17)") (class "Default")
      (node (ref "U3") (pin "17") (pinfunction "PA7_17") (pintype "bidirectional+no_connect"))
    )
    (net (code "78") (name "unconnected-(U3-PB1-Pad19)") (class "Default")
      (node (ref "U3") (pin "19") (pinfunction "PB1_19") (pintype "input+no_connect"))
    )
    (net (code "79") (name "unconnected-(U3-PB4{slash}JNTRST-Pad40)") (class "Default")
      (node (ref "U3") (pin "40") (pinfunction "PB4/JNTRST_40") (pintype "bidirectional+no_connect"))
    )
    (net (code "80") (name "unconnected-(U3-PB5-Pad41)") (class "Default")
      (node (ref "U3") (pin "41") (pinfunction "PB5_41") (pintype "bidirectional+no_connect"))
    )
    (net (code "81") (name "unconnected-(U3-PB6-Pad42)") (class "Default")
      (node (ref "U3") (pin "42") (pinfunction "PB6_42") (pintype "bidirectional+no_connect"))
    )
    (net (code "82") (name "unconnected-(U3-PB8-Pad45)") (class "Default")
      (node (ref "U3") (pin "45") (pinfunction "PB8_45") (pintype "bidirectional+no_connect"))
    )
    (net (code "83") (name "unconnected-(U3-PB11-Pad22)") (class "Default")
      (node (ref "U3") (pin "22") (pinfunction "PB11_22") (pintype "bidirectional+no_connect"))
    )
    (net (code "84") (name "unconnected-(U3-PC15-Pad4)") (class "Default")
      (node (ref "U3") (pin "4") (pinfunction "PC15_4") (pintype "bidirectional+no_connect"))
    )
    (net (code "85") (name "unconnected-(U4-NC-Pad5)") (class "Default")
      (node (ref "U4") (pin "5") (pinfunction "NC_5") (pintype "passive+no_connect"))
    )
    (net (code "86") (name "unconnected-(U4-PG-Pad3)") (class "Default")
      (node (ref "U4") (pin "3") (pinfunction "PG_3") (pintype "passive+no_connect"))
    )
  )
)
